# ST-LINK.net
KiCad netlist of a schematic drawn in Altium Designer
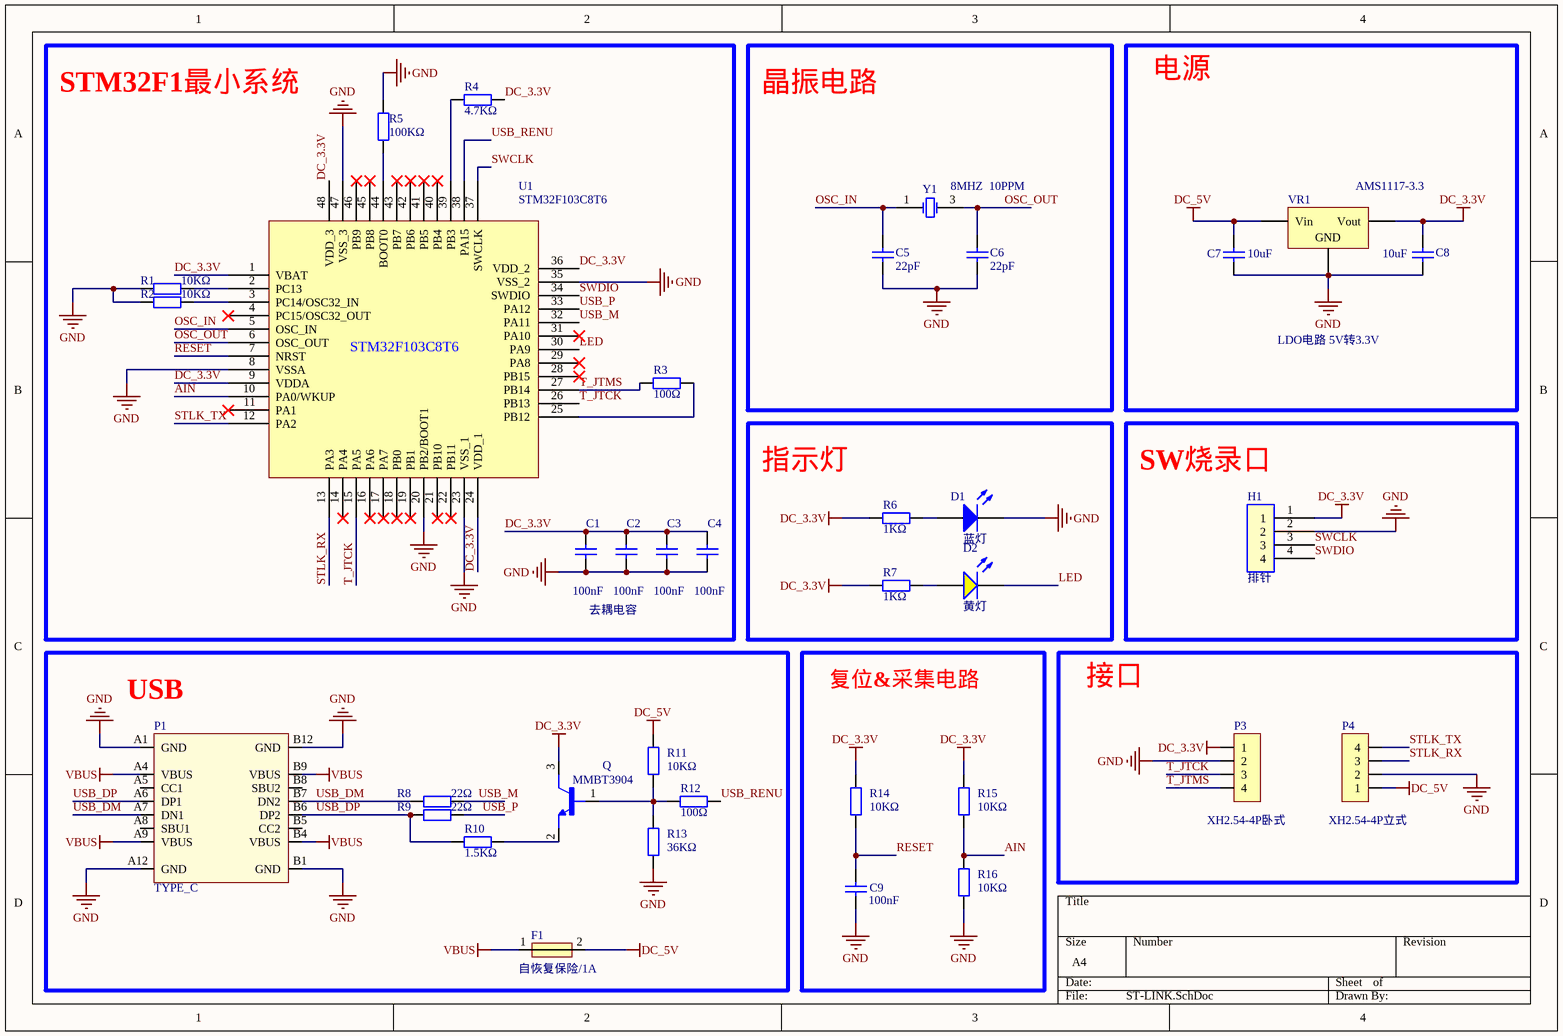
[diagram p0: ST-LINK.SchDoc]

(export (version "E")
  (design (tool "Eeschema 10.0.6"))
  (components
    (comp (ref "C1")
      (value "100nF")
      (footprint "0603_C")
      (description "贴片电容")
      (libsource (lib "Miscellaneous Devices LC") (part "0603 100nF (104) 10% 50V"))
    )
    (comp (ref "C2")
      (value "100nF")
      (footprint "0603_C")
      (description "贴片电容")
      (libsource (lib "Miscellaneous Devices LC") (part "0603 100nF (104) 10% 50V"))
    )
    (comp (ref "C3")
      (value "100nF")
      (footprint "0603_C")
      (description "贴片电容")
      (libsource (lib "Miscellaneous Devices LC") (part "0603 100nF (104) 10% 50V"))
    )
    (comp (ref "C4")
      (value "100nF")
      (footprint "0603_C")
      (description "贴片电容")
      (libsource (lib "Miscellaneous Devices LC") (part "0603 100nF (104) 10% 50V"))
    )
    (comp (ref "C5")
      (value "22pF")
      (footprint "0603_C")
      (description "贴片电容")
      (libsource (lib "Miscellaneous Devices LC") (part "0603 22pF (220) 5% 50V"))
    )
    (comp (ref "C6")
      (value "22pF")
      (footprint "0603_C")
      (description "贴片电容")
      (libsource (lib "Miscellaneous Devices LC") (part "0603 22pF (220) 5% 50V"))
    )
    (comp (ref "C7")
      (value "10uF")
      (footprint "0603_C")
      (description "贴片电容")
      (libsource (lib "Miscellaneous Devices LC") (part "0603 10uF (106) 10% 10V"))
    )
    (comp (ref "C8")
      (value "10uF")
      (footprint "0603_C")
      (description "贴片电容")
      (libsource (lib "Miscellaneous Devices LC") (part "0603 10uF (106) 10% 10V"))
    )
    (comp (ref "C9")
      (value "100nF")
      (footprint "0603_C")
      (description "贴片电容")
      (libsource (lib "Miscellaneous Devices LC") (part "0603 100nF (104) 10% 50V"))
    )
    (comp (ref "D1")
      (value "蓝灯")
      (footprint "0603_LED_S1")
      (description "发光二极管")
      (libsource (lib "Miscellaneous Devices LC") (part "0603 蓝灯"))
    )
    (comp (ref "D2")
      (value "黄灯")
      (footprint "0603_LED_S1")
      (description "发光二极管")
      (libsource (lib "Miscellaneous Devices LC") (part "0603 黄灯"))
    )
    (comp (ref "F1")
      (value "自恢复保险/1A")
      (footprint "0805_R")
      (description "保险丝")
      (libsource (lib "Other_Library") (part "保险丝0805（自恢复）"))
    )
    (comp (ref "H1")
      (value "排针")
      (footprint "HDR2.54-LI-4P")
      (libsource (lib "Switch - button - interface") (part "排针HDR2.54-LI-4P"))
    )
    (comp (ref "P1")
      (value "TYPE_C")
      (footprint "Type-C_16P")
      (description "USB接口")
      (libsource (lib "Switch - button - interface") (part "Tpye C 16线母座"))
    )
    (comp (ref "P3")
      (value "XH2.54-4P卧式")
      (footprint "XH2.54_4P卧式")
      (description "XH2.54-2P接口")
      (libsource (lib "Switch - button - interface") (part "XH2.54-4P卧式"))
    )
    (comp (ref "P4")
      (value "XH2.54-4P立式")
      (footprint "XH2.54_4P立式")
      (description "XH2.54-2P接口")
      (libsource (lib "Switch - button - interface") (part "XH2.54-4P立式"))
    )
    (comp (ref "Q")
      (value "MMBT3904")
      (footprint "SOT95P240X120-3N")
      (description "三极管NPN(BJT)")
      (fields (field (name "MF") "STMicroelectronics"))
      (libsource (lib "Other_Library") (part "MMBT3904"))
    )
    (comp (ref "R1")
      (value "10KΩ")
      (footprint "0603_R")
      (description "贴片电阻")
      (libsource (lib "Miscellaneous Devices LC") (part "0603 10KΩ (1002) 1%"))
    )
    (comp (ref "R2")
      (value "10KΩ")
      (footprint "0603_R")
      (description "贴片电阻")
      (libsource (lib "Miscellaneous Devices LC") (part "0603 10KΩ (1002) 1%"))
    )
    (comp (ref "R3")
      (value "100Ω")
      (footprint "0603_R")
      (description "贴片电阻")
      (libsource (lib "Miscellaneous Devices LC") (part "0603 100Ω (1000) 1%"))
    )
    (comp (ref "R4")
      (value "4.7KΩ")
      (footprint "0603_R")
      (description "贴片电阻")
      (libsource (lib "Miscellaneous Devices LC") (part "0603 4.7KΩ (4701) 1%"))
    )
    (comp (ref "R5")
      (value "100KΩ")
      (footprint "0603_R")
      (description "贴片电阻")
      (libsource (lib "Miscellaneous Devices LC") (part "0603 100KΩ (1003) 1%"))
    )
    (comp (ref "R6")
      (value "1KΩ")
      (footprint "0603_R")
      (description "贴片电阻")
      (libsource (lib "Miscellaneous Devices LC") (part "0603 1KΩ (1001) 1%"))
    )
    (comp (ref "R7")
      (value "1KΩ")
      (footprint "0603_R")
      (description "贴片电阻")
      (libsource (lib "Miscellaneous Devices LC") (part "0603 1KΩ (1001) 1%"))
    )
    (comp (ref "R8")
      (value "22Ω")
      (footprint "0603_R")
      (description "贴片电阻")
      (libsource (lib "Miscellaneous Devices LC") (part "0603 22Ω (22R0) 1%"))
    )
    (comp (ref "R9")
      (value "22Ω")
      (footprint "0603_R")
      (description "贴片电阻")
      (libsource (lib "Miscellaneous Devices LC") (part "0603 22Ω (22R0) 1%"))
    )
    (comp (ref "R10")
      (value "1.5KΩ")
      (footprint "0603_R")
      (description "贴片电阻")
      (libsource (lib "Miscellaneous Devices LC") (part "0603 1.5KΩ (1501) 1%"))
    )
    (comp (ref "R11")
      (value "10KΩ")
      (footprint "0603_R")
      (description "贴片电阻")
      (libsource (lib "") (part "0603 10KΩ (1002) 1%_1"))
    )
    (comp (ref "R12")
      (value "100Ω")
      (footprint "0603_R")
      (description "贴片电阻")
      (libsource (lib "Miscellaneous Devices LC") (part "0603 100Ω (1000) 1%"))
    )
    (comp (ref "R13")
      (value "36KΩ")
      (footprint "0603_R")
      (description "贴片电阻")
      (libsource (lib "Miscellaneous Devices LC") (part "0603 36KΩ (3602) 1%"))
    )
    (comp (ref "R14")
      (value "10KΩ")
      (footprint "0603_R")
      (description "贴片电阻")
      (libsource (lib "") (part "0603 10KΩ (1002) 1%_1"))
    )
    (comp (ref "R15")
      (value "10KΩ")
      (footprint "0603_R")
      (description "贴片电阻")
      (libsource (lib "") (part "0603 10KΩ (1002) 1%_1"))
    )
    (comp (ref "R16")
      (value "10KΩ")
      (footprint "0603_R")
      (description "贴片电阻")
      (libsource (lib "") (part "0603 10KΩ (1002) 1%_1"))
    )
    (comp (ref "U1")
      (value "STM32F103C8T6")
      (footprint "STM32F103C8T6")
      (description "STM32芯片")
      (libsource (lib "MCU") (part "STM32F103C8T6"))
    )
    (comp (ref "VR1")
      (value "AMS1117-3.3")
      (footprint "SOT-223")
      (description "低压差线性稳压(LDO)")
      (libsource (lib "Miscellaneous Devices LC") (part "SOT-223 AMS1117-3.3"))
    )
    (comp (ref "Y1")
      (value "8MHZ  10PPM")
      (footprint "SMD-3225_4P")
      (description "贴片晶振")
      (libsource (lib "Miscellaneous Devices LC") (part "SMD-3225_4P  16MHZ 9PF 10PPM"))
    )
  )
  (nets
    (net (code "1") (name "/AIN") (class "Default")
      (node (ref "R15") (pin "1") (pinfunction "1_1") (pintype "passive"))
      (node (ref "R16") (pin "2") (pinfunction "2_2") (pintype "passive"))
      (node (ref "U1") (pin "10") (pinfunction "PA0/WKUP_10") (pintype "passive"))
    )
    (net (code "2") (name "/LED") (class "Default")
      (node (ref "D2") (pin "K") (pinfunction "K_K") (pintype "passive"))
      (node (ref "U1") (pin "30") (pinfunction "PA9_30") (pintype "passive"))
    )
    (net (code "3") (name "/OSC_IN") (class "Default")
      (node (ref "C5") (pin "1") (pinfunction "1_1") (pintype "passive"))
      (node (ref "U1") (pin "5") (pinfunction "OSC_IN_5") (pintype "passive"))
      (node (ref "Y1") (pin "1") (pinfunction "OSC1_1") (pintype "passive"))
    )
    (net (code "4") (name "/OSC_OUT") (class "Default")
      (node (ref "C6") (pin "1") (pinfunction "1_1") (pintype "passive"))
      (node (ref "U1") (pin "6") (pinfunction "OSC_OUT_6") (pintype "passive"))
      (node (ref "Y1") (pin "3") (pinfunction "OSC2_3") (pintype "passive"))
    )
    (net (code "5") (name "/RESET") (class "Default")
      (node (ref "C9") (pin "2") (pinfunction "2_2") (pintype "passive"))
      (node (ref "R14") (pin "1") (pinfunction "1_1") (pintype "passive"))
      (node (ref "U1") (pin "7") (pinfunction "NRST_7") (pintype "passive"))
    )
    (net (code "6") (name "/STLK_RX") (class "Default")
      (node (ref "P4") (pin "3") (pinfunction "3_3") (pintype "passive"))
      (node (ref "U1") (pin "13") (pinfunction "PA3_13") (pintype "passive"))
    )
    (net (code "7") (name "/STLK_TX") (class "Default")
      (node (ref "P4") (pin "4") (pinfunction "4_4") (pintype "passive"))
      (node (ref "U1") (pin "12") (pinfunction "PA2_12") (pintype "passive"))
    )
    (net (code "8") (name "/SWCLK") (class "Default")
      (node (ref "H1") (pin "3") (pinfunction "3_3") (pintype "passive"))
      (node (ref "U1") (pin "37") (pinfunction "SWCLK_37") (pintype "passive"))
    )
    (net (code "9") (name "/SWDIO") (class "Default")
      (node (ref "H1") (pin "4") (pinfunction "4_4") (pintype "passive"))
      (node (ref "U1") (pin "34") (pinfunction "SWDIO_34") (pintype "passive"))
    )
    (net (code "10") (name "/T_JTCK") (class "Default")
      (node (ref "P3") (pin "3") (pinfunction "3_3") (pintype "passive"))
      (node (ref "U1") (pin "15") (pinfunction "PA5_15") (pintype "passive"))
      (node (ref "U1") (pin "26") (pinfunction "PB13_26") (pintype "passive"))
    )
    (net (code "11") (name "/T_JTMS") (class "Default")
      (node (ref "P3") (pin "4") (pinfunction "4_4") (pintype "passive"))
      (node (ref "R3") (pin "1") (pinfunction "1_1") (pintype "passive"))
      (node (ref "U1") (pin "27") (pinfunction "PB14_27") (pintype "passive"))
    )
    (net (code "12") (name "/USB_DM") (class "Default")
      (node (ref "P1") (pin "A7") (pinfunction "DN1_A7") (pintype "passive"))
      (node (ref "P1") (pin "B7") (pinfunction "DN2_B7") (pintype "passive"))
      (node (ref "R8") (pin "1") (pinfunction "1_1") (pintype "passive"))
    )
    (net (code "13") (name "/USB_DP") (class "Default")
      (node (ref "P1") (pin "A6") (pinfunction "DP1_A6") (pintype "passive"))
      (node (ref "P1") (pin "B6") (pinfunction "DP2_B6") (pintype "passive"))
      (node (ref "R10") (pin "2") (pinfunction "2_2") (pintype "passive"))
      (node (ref "R9") (pin "1") (pinfunction "1_1") (pintype "passive"))
    )
    (net (code "14") (name "/USB_M") (class "Default")
      (node (ref "R8") (pin "2") (pinfunction "2_2") (pintype "passive"))
      (node (ref "U1") (pin "32") (pinfunction "PA11_32") (pintype "passive"))
    )
    (net (code "15") (name "/USB_P") (class "Default")
      (node (ref "R9") (pin "2") (pinfunction "2_2") (pintype "passive"))
      (node (ref "U1") (pin "33") (pinfunction "PA12_33") (pintype "passive"))
    )
    (net (code "16") (name "/USB_RENU") (class "Default")
      (node (ref "R12") (pin "2") (pinfunction "2_2") (pintype "passive"))
      (node (ref "U1") (pin "38") (pinfunction "PA15_38") (pintype "passive"))
    )
    (net (code "17") (name "DC_3.3V") (class "Default")
      (node (ref "C1") (pin "2") (pinfunction "2_2") (pintype "passive"))
      (node (ref "C2") (pin "2") (pinfunction "2_2") (pintype "passive"))
      (node (ref "C3") (pin "2") (pinfunction "2_2") (pintype "passive"))
      (node (ref "C4") (pin "2") (pinfunction "2_2") (pintype "passive"))
      (node (ref "C8") (pin "2") (pinfunction "2_2") (pintype "passive"))
      (node (ref "H1") (pin "1") (pinfunction "1_1") (pintype "passive"))
      (node (ref "P3") (pin "1") (pinfunction "1_1") (pintype "passive"))
      (node (ref "Q") (pin "3") (pinfunction "C_3") (pintype "passive"))
      (node (ref "R14") (pin "2") (pinfunction "2_2") (pintype "passive"))
      (node (ref "R15") (pin "2") (pinfunction "2_2") (pintype "passive"))
      (node (ref "R4") (pin "2") (pinfunction "2_2") (pintype "passive"))
      (node (ref "R6") (pin "1") (pinfunction "1_1") (pintype "passive"))
      (node (ref "R7") (pin "1") (pinfunction "1_1") (pintype "passive"))
      (node (ref "U1") (pin "1") (pinfunction "VBAT_1") (pintype "passive"))
      (node (ref "U1") (pin "24") (pinfunction "VDD_1_24") (pintype "passive"))
      (node (ref "U1") (pin "36") (pinfunction "VDD_2_36") (pintype "passive"))
      (node (ref "U1") (pin "48") (pinfunction "VDD_3_48") (pintype "passive"))
      (node (ref "U1") (pin "9") (pinfunction "VDDA_9") (pintype "passive"))
      (node (ref "VR1") (pin "2") (pinfunction "Vout_2") (pintype "passive"))
    )
    (net (code "18") (name "DC_5V") (class "Default")
      (node (ref "C7") (pin "1") (pinfunction "1_1") (pintype "passive"))
      (node (ref "F1") (pin "2") (pintype "passive"))
      (node (ref "P4") (pin "1") (pinfunction "1_1") (pintype "passive"))
      (node (ref "R11") (pin "2") (pinfunction "2_2") (pintype "passive"))
      (node (ref "VR1") (pin "3") (pinfunction "Vin_3") (pintype "passive"))
    )
    (net (code "19") (name "GND") (class "Default")
      (node (ref "C1") (pin "1") (pinfunction "1_1") (pintype "passive"))
      (node (ref "C2") (pin "1") (pinfunction "1_1") (pintype "passive"))
      (node (ref "C3") (pin "1") (pinfunction "1_1") (pintype "passive"))
      (node (ref "C4") (pin "1") (pinfunction "1_1") (pintype "passive"))
      (node (ref "C5") (pin "2") (pinfunction "2_2") (pintype "passive"))
      (node (ref "C6") (pin "2") (pinfunction "2_2") (pintype "passive"))
      (node (ref "C7") (pin "2") (pinfunction "2_2") (pintype "passive"))
      (node (ref "C8") (pin "1") (pinfunction "1_1") (pintype "passive"))
      (node (ref "C9") (pin "1") (pinfunction "1_1") (pintype "passive"))
      (node (ref "D1") (pin "K") (pinfunction "K_K") (pintype "passive"))
      (node (ref "H1") (pin "2") (pinfunction "2_2") (pintype "passive"))
      (node (ref "P1") (pin "A1") (pinfunction "GND_A1") (pintype "passive"))
      (node (ref "P1") (pin "A12") (pinfunction "GND_A12") (pintype "passive"))
      (node (ref "P1") (pin "B1") (pinfunction "GND_B1") (pintype "passive"))
      (node (ref "P1") (pin "B12") (pinfunction "GND_B12") (pintype "passive"))
      (node (ref "P3") (pin "2") (pinfunction "2_2") (pintype "passive"))
      (node (ref "P4") (pin "2") (pinfunction "2_2") (pintype "passive"))
      (node (ref "R1") (pin "1") (pinfunction "1_1") (pintype "passive"))
      (node (ref "R13") (pin "1") (pinfunction "1_1") (pintype "passive"))
      (node (ref "R16") (pin "1") (pinfunction "1_1") (pintype "passive"))
      (node (ref "R2") (pin "1") (pinfunction "1_1") (pintype "passive"))
      (node (ref "R5") (pin "2") (pinfunction "2_2") (pintype "passive"))
      (node (ref "U1") (pin "20") (pinfunction "PB2/BOOT1_20") (pintype "passive"))
      (node (ref "U1") (pin "23") (pinfunction "VSS_1_23") (pintype "passive"))
      (node (ref "U1") (pin "35") (pinfunction "VSS_2_35") (pintype "passive"))
      (node (ref "U1") (pin "47") (pinfunction "VSS_3_47") (pintype "passive"))
      (node (ref "U1") (pin "8") (pinfunction "VSSA_8") (pintype "passive"))
      (node (ref "VR1") (pin "1") (pinfunction "GND_1") (pintype "passive"))
    )
    (net (code "20") (name "Net-(D1-PadA)") (class "Default")
      (node (ref "D1") (pin "A") (pinfunction "A_A") (pintype "passive"))
      (node (ref "R6") (pin "2") (pinfunction "2_2") (pintype "passive"))
    )
    (net (code "21") (name "Net-(D2-PadA)") (class "Default")
      (node (ref "D2") (pin "A") (pinfunction "A_A") (pintype "passive"))
      (node (ref "R7") (pin "2") (pinfunction "2_2") (pintype "passive"))
    )
    (net (code "22") (name "Net-(Q-B)") (class "Default")
      (node (ref "Q") (pin "1") (pinfunction "B_1") (pintype "passive"))
      (node (ref "R11") (pin "1") (pinfunction "1_1") (pintype "passive"))
      (node (ref "R12") (pin "1") (pinfunction "1_1") (pintype "passive"))
      (node (ref "R13") (pin "2") (pinfunction "2_2") (pintype "passive"))
    )
    (net (code "23") (name "Net-(Q-E)") (class "Default")
      (node (ref "Q") (pin "2") (pinfunction "E_2") (pintype "passive"))
      (node (ref "R10") (pin "1") (pinfunction "1_1") (pintype "passive"))
    )
    (net (code "24") (name "Net-(U1-BOOT0)") (class "Default")
      (node (ref "R5") (pin "1") (pinfunction "1_1") (pintype "passive"))
      (node (ref "U1") (pin "44") (pinfunction "BOOT0_44") (pintype "passive"))
    )
    (net (code "25") (name "Net-(U1-PB3)") (class "Default")
      (node (ref "R4") (pin "1") (pinfunction "1_1") (pintype "passive"))
      (node (ref "U1") (pin "39") (pinfunction "PB3_39") (pintype "passive"))
    )
    (net (code "26") (name "Net-(U1-PB12)") (class "Default")
      (node (ref "R3") (pin "2") (pinfunction "2_2") (pintype "passive"))
      (node (ref "U1") (pin "25") (pinfunction "PB12_25") (pintype "passive"))
    )
    (net (code "27") (name "Net-(U1-PC13)") (class "Default")
      (node (ref "R1") (pin "2") (pinfunction "2_2") (pintype "passive"))
      (node (ref "U1") (pin "2") (pinfunction "PC13_2") (pintype "passive"))
    )
    (net (code "28") (name "Net-(U1-PC14{slash}OSC32_IN)") (class "Default")
      (node (ref "R2") (pin "2") (pinfunction "2_2") (pintype "passive"))
      (node (ref "U1") (pin "3") (pinfunction "PC14/OSC32_IN_3") (pintype "passive"))
    )
    (net (code "29") (name "VBUS") (class "Default")
      (node (ref "F1") (pin "1") (pintype "passive"))
      (node (ref "P1") (pin "A4") (pinfunction "VBUS_A4") (pintype "passive"))
      (node (ref "P1") (pin "A9") (pinfunction "VBUS_A9") (pintype "passive"))
      (node (ref "P1") (pin "B4") (pinfunction "VBUS_B4") (pintype "passive"))
      (node (ref "P1") (pin "B9") (pinfunction "VBUS_B9") (pintype "passive"))
    )
    (net (code "30") (name "unconnected-(P1-CC1-PadA5)") (class "Default")
      (node (ref "P1") (pin "A5") (pinfunction "CC1_A5") (pintype "passive"))
    )
    (net (code "31") (name "unconnected-(P1-CC2-PadB5)") (class "Default")
      (node (ref "P1") (pin "B5") (pinfunction "CC2_B5") (pintype "passive"))
    )
    (net (code "32") (name "unconnected-(P1-SBU1-PadA8)") (class "Default")
      (node (ref "P1") (pin "A8") (pinfunction "SBU1_A8") (pintype "passive"))
    )
    (net (code "33") (name "unconnected-(P1-SBU2-PadB8)") (class "Default")
      (node (ref "P1") (pin "B8") (pinfunction "SBU2_B8") (pintype "passive"))
    )
    (net (code "34") (name "unconnected-(U1-PA1-Pad11)") (class "Default")
      (node (ref "U1") (pin "11") (pinfunction "PA1_11") (pintype "passive+no_connect"))
    )
    (net (code "35") (name "unconnected-(U1-PA4-Pad14)") (class "Default")
      (node (ref "U1") (pin "14") (pinfunction "PA4_14") (pintype "passive+no_connect"))
    )
    (net (code "36") (name "unconnected-(U1-PA6-Pad16)") (class "Default")
      (node (ref "U1") (pin "16") (pinfunction "PA6_16") (pintype "passive+no_connect"))
    )
    (net (code "37") (name "unconnected-(U1-PA7-Pad17)") (class "Default")
      (node (ref "U1") (pin "17") (pinfunction "PA7_17") (pintype "passive+no_connect"))
    )
    (net (code "38") (name "unconnected-(U1-PA8-Pad29)") (class "Default")
      (node (ref "U1") (pin "29") (pinfunction "PA8_29") (pintype "passive+no_connect"))
    )
    (net (code "39") (name "unconnected-(U1-PA10-Pad31)") (class "Default")
      (node (ref "U1") (pin "31") (pinfunction "PA10_31") (pintype "passive+no_connect"))
    )
    (net (code "40") (name "unconnected-(U1-PB0-Pad18)") (class "Default")
      (node (ref "U1") (pin "18") (pinfunction "PB0_18") (pintype "passive+no_connect"))
    )
    (net (code "41") (name "unconnected-(U1-PB1-Pad19)") (class "Default")
      (node (ref "U1") (pin "19") (pinfunction "PB1_19") (pintype "passive+no_connect"))
    )
    (net (code "42") (name "unconnected-(U1-PB4-Pad40)") (class "Default")
      (node (ref "U1") (pin "40") (pinfunction "PB4_40") (pintype "passive+no_connect"))
    )
    (net (code "43") (name "unconnected-(U1-PB5-Pad41)") (class "Default")
      (node (ref "U1") (pin "41") (pinfunction "PB5_41") (pintype "passive+no_connect"))
    )
    (net (code "44") (name "unconnected-(U1-PB6-Pad42)") (class "Default")
      (node (ref "U1") (pin "42") (pinfunction "PB6_42") (pintype "passive+no_connect"))
    )
    (net (code "45") (name "unconnected-(U1-PB7-Pad43)") (class "Default")
      (node (ref "U1") (pin "43") (pinfunction "PB7_43") (pintype "passive+no_connect"))
    )
    (net (code "46") (name "unconnected-(U1-PB8-Pad45)") (class "Default")
      (node (ref "U1") (pin "45") (pinfunction "PB8_45") (pintype "passive+no_connect"))
    )
    (net (code "47") (name "unconnected-(U1-PB9-Pad46)") (class "Default")
      (node (ref "U1") (pin "46") (pinfunction "PB9_46") (pintype "passive+no_connect"))
    )
    (net (code "48") (name "unconnected-(U1-PB10-Pad21)") (class "Default")
      (node (ref "U1") (pin "21") (pinfunction "PB10_21") (pintype "passive+no_connect"))
    )
    (net (code "49") (name "unconnected-(U1-PB11-Pad22)") (class "Default")
      (node (ref "U1") (pin "22") (pinfunction "PB11_22") (pintype "passive+no_connect"))
    )
    (net (code "50") (name "unconnected-(U1-PB15-Pad28)") (class "Default")
      (node (ref "U1") (pin "28") (pinfunction "PB15_28") (pintype "passive+no_connect"))
    )
    (net (code "51") (name "unconnected-(U1-PC15{slash}OSC32_OUT-Pad4)") (class "Default")
      (node (ref "U1") (pin "4") (pinfunction "PC15/OSC32_OUT_4") (pintype "passive+no_connect"))
    )
  )
)
